# Soraduino_logsc.net
KiCad netlist of a schematic drawn in EAGLE
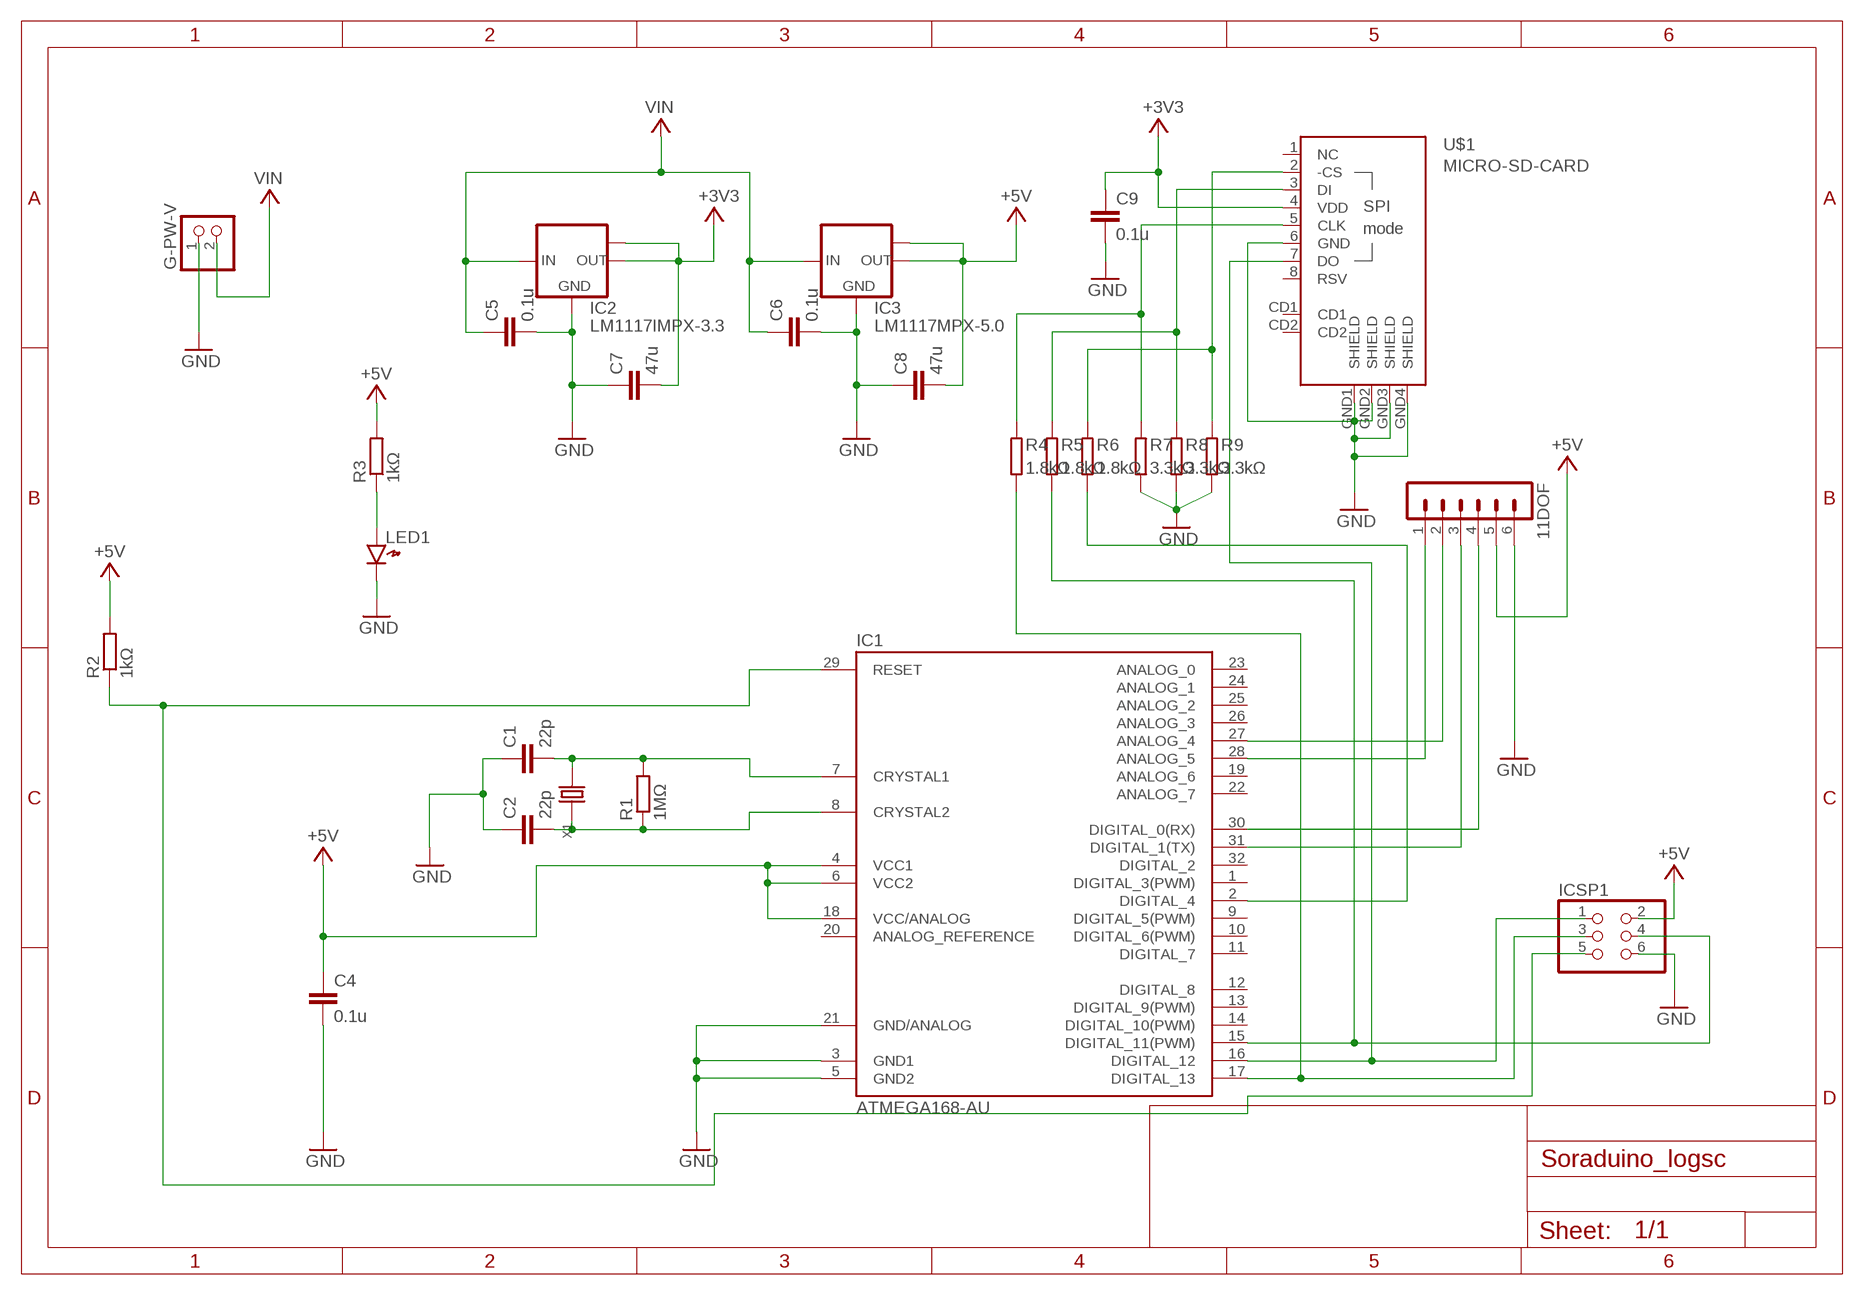
[diagram p0: schematic, sheet 1]

(export (version "E")
  (design (tool "Eeschema 10.0.6"))
  (components
    (comp (ref "11DOF")
      (value "MA06-1")
      (footprint "eagle-import:MA06-1")
      (libsource (lib "eagle-import") (part "MA06-1"))
    )
    (comp (ref "C1")
      (value "22p")
      (footprint "eagle-import:C1608")
      (libsource (lib "eagle-import") (part "C-EUC1608"))
    )
    (comp (ref "C2")
      (value "22p")
      (footprint "eagle-import:C1608")
      (libsource (lib "eagle-import") (part "C-EUC1608"))
    )
    (comp (ref "C4")
      (value "0.1u")
      (footprint "eagle-import:C2012")
      (libsource (lib "eagle-import") (part "C-EUC2012"))
    )
    (comp (ref "C5")
      (value "0.1u")
      (footprint "eagle-import:C2012")
      (libsource (lib "eagle-import") (part "C-EUC2012"))
    )
    (comp (ref "C6")
      (value "0.1u")
      (footprint "eagle-import:C2012")
      (libsource (lib "eagle-import") (part "C-EUC2012"))
    )
    (comp (ref "C7")
      (value "47u")
      (footprint "eagle-import:C3225")
      (libsource (lib "eagle-import") (part "C-EUC3225"))
    )
    (comp (ref "C8")
      (value "47u")
      (footprint "eagle-import:C3225")
      (libsource (lib "eagle-import") (part "C-EUC3225"))
    )
    (comp (ref "C9")
      (value "0.1u")
      (footprint "eagle-import:C2012")
      (libsource (lib "eagle-import") (part "C-EUC2012"))
    )
    (comp (ref "G-PW-V")
      (value "PINHD-1X2")
      (footprint "eagle-import:1X02")
      (libsource (lib "eagle-import") (part "PINHD-1X2"))
    )
    (comp (ref "IC1")
      (value "ATMEGA168-AU")
      (footprint "eagle-import:TQFP32-08")
      (libsource (lib "eagle-import") (part "ATMEGA168-AU"))
    )
    (comp (ref "IC2")
      (value "LM1117IMPX-3.3")
      (footprint "eagle-import:SOT223")
      (libsource (lib "eagle-import") (part "LM1117IMPX-3.3"))
    )
    (comp (ref "IC3")
      (value "LM1117MPX-5.0")
      (footprint "eagle-import:SOT223")
      (libsource (lib "eagle-import") (part "LM1117MPX-5.0"))
    )
    (comp (ref "ICSP1")
      (value "PINHD-2X3")
      (footprint "eagle-import:2X03")
      (libsource (lib "eagle-import") (part "PINHD-2X3"))
    )
    (comp (ref "LED1")
      (value "LED1608")
      (footprint "eagle-import:LED1608")
      (libsource (lib "eagle-import") (part "LED1608"))
    )
    (comp (ref "R1")
      (value "1MΩ")
      (footprint "eagle-import:R0603")
      (libsource (lib "eagle-import") (part "R-EU_R0603"))
    )
    (comp (ref "R2")
      (value "1kΩ")
      (footprint "eagle-import:R0603")
      (libsource (lib "eagle-import") (part "R-EU_R0603"))
    )
    (comp (ref "R3")
      (value "1kΩ")
      (footprint "eagle-import:R0603")
      (libsource (lib "eagle-import") (part "R-EU_R0603"))
    )
    (comp (ref "R4")
      (value "1.8kΩ")
      (footprint "eagle-import:SMD1608")
      (libsource (lib "eagle-import") (part "RESISTOR1608"))
    )
    (comp (ref "R5")
      (value "1.8kΩ")
      (footprint "eagle-import:SMD1608")
      (libsource (lib "eagle-import") (part "RESISTOR1608"))
    )
    (comp (ref "R6")
      (value "1.8kΩ")
      (footprint "eagle-import:SMD1608")
      (libsource (lib "eagle-import") (part "RESISTOR1608"))
    )
    (comp (ref "R7")
      (value "3.3kΩ")
      (footprint "eagle-import:SMD1608")
      (libsource (lib "eagle-import") (part "RESISTOR1608"))
    )
    (comp (ref "R8")
      (value "3.3kΩ")
      (footprint "eagle-import:SMD1608")
      (libsource (lib "eagle-import") (part "RESISTOR1608"))
    )
    (comp (ref "R9")
      (value "3.3kΩ")
      (footprint "eagle-import:SMD1608")
      (libsource (lib "eagle-import") (part "RESISTOR1608"))
    )
    (comp (ref "U$1")
      (value "MICRO-SD-CARD")
      (footprint "eagle-import:DM3AT-SF-PEJ")
      (libsource (lib "eagle-import") (part "MICRO-SD-CARD"))
    )
    (comp (ref "X1")
      (value "CRYSTAL'3225'")
      (footprint "eagle-import:4P-SMD-3.2X2.5")
      (libsource (lib "eagle-import") (part "CRYSTAL'3225'"))
    )
  )
  (nets
    (net (code "1") (name "+3V3") (class "Default")
      (node (ref "C7") (pin "2") (pinfunction "2_2") (pintype "passive"))
      (node (ref "C9") (pin "1") (pinfunction "1_1") (pintype "passive"))
      (node (ref "IC2") (pin "2") (pinfunction "OUT_2") (pintype "passive"))
      (node (ref "IC2") (pin "TAB") (pinfunction "OUT1_TAB") (pintype "passive"))
      (node (ref "U$1") (pin "4") (pinfunction "VDD_4") (pintype "bidirectional"))
    )
    (net (code "2") (name "+5V") (class "Default")
      (node (ref "11DOF") (pin "5") (pinfunction "5_5") (pintype "passive"))
      (node (ref "C4") (pin "1") (pinfunction "1_1") (pintype "passive"))
      (node (ref "C8") (pin "2") (pinfunction "2_2") (pintype "passive"))
      (node (ref "IC1") (pin "18") (pinfunction "VCC/ANALOG_18") (pintype "passive"))
      (node (ref "IC1") (pin "4") (pinfunction "VCC1_4") (pintype "power_in"))
      (node (ref "IC1") (pin "6") (pinfunction "VCC2_6") (pintype "power_in"))
      (node (ref "IC3") (pin "2") (pinfunction "OUT_2") (pintype "passive"))
      (node (ref "IC3") (pin "TAB") (pinfunction "OUT1_TAB") (pintype "passive"))
      (node (ref "ICSP1") (pin "2") (pinfunction "2_2") (pintype "passive"))
      (node (ref "R2") (pin "2") (pinfunction "2_2") (pintype "passive"))
      (node (ref "R3") (pin "2") (pinfunction "2_2") (pintype "passive"))
    )
    (net (code "3") (name "GND") (class "Default")
      (node (ref "11DOF") (pin "6") (pinfunction "6_6") (pintype "passive"))
      (node (ref "C1") (pin "1") (pinfunction "1_1") (pintype "passive"))
      (node (ref "C2") (pin "1") (pinfunction "1_1") (pintype "passive"))
      (node (ref "C4") (pin "2") (pinfunction "2_2") (pintype "passive"))
      (node (ref "C5") (pin "2") (pinfunction "2_2") (pintype "passive"))
      (node (ref "C6") (pin "2") (pinfunction "2_2") (pintype "passive"))
      (node (ref "C7") (pin "1") (pinfunction "1_1") (pintype "passive"))
      (node (ref "C8") (pin "1") (pinfunction "1_1") (pintype "passive"))
      (node (ref "C9") (pin "2") (pinfunction "2_2") (pintype "passive"))
      (node (ref "G-PW-V") (pin "1") (pinfunction "1_1") (pintype "passive"))
      (node (ref "IC1") (pin "21") (pinfunction "GND/ANALOG_21") (pintype "power_in"))
      (node (ref "IC1") (pin "3") (pinfunction "GND1_3") (pintype "power_in"))
      (node (ref "IC1") (pin "5") (pinfunction "GND2_5") (pintype "power_in"))
      (node (ref "IC2") (pin "1") (pinfunction "GND_1") (pintype "input"))
      (node (ref "IC3") (pin "1") (pinfunction "GND_1") (pintype "input"))
      (node (ref "ICSP1") (pin "6") (pinfunction "6_6") (pintype "passive"))
      (node (ref "LED1") (pin "K") (pinfunction "K_K") (pintype "passive"))
      (node (ref "R7") (pin "2") (pinfunction "2_2") (pintype "passive"))
      (node (ref "R8") (pin "2") (pinfunction "2_2") (pintype "passive"))
      (node (ref "R9") (pin "2") (pinfunction "2_2") (pintype "passive"))
      (node (ref "U$1") (pin "6") (pinfunction "GND_6") (pintype "bidirectional"))
      (node (ref "U$1") (pin "GND1") (pinfunction "SHIELD_GND1") (pintype "bidirectional"))
      (node (ref "U$1") (pin "GND2") (pinfunction "SHIELD_GND2") (pintype "bidirectional"))
      (node (ref "U$1") (pin "GND3") (pinfunction "SHIELD_GND3") (pintype "bidirectional"))
      (node (ref "U$1") (pin "GND4") (pinfunction "SHIELD_GND4") (pintype "bidirectional"))
    )
    (net (code "4") (name "Net-(IC1-ANALOG_4)") (class "Default")
      (node (ref "11DOF") (pin "2") (pinfunction "2_2") (pintype "passive"))
      (node (ref "IC1") (pin "27") (pinfunction "ANALOG_4_27") (pintype "bidirectional"))
    )
    (net (code "5") (name "Net-(IC1-ANALOG_5)") (class "Default")
      (node (ref "11DOF") (pin "1") (pinfunction "1_1") (pintype "passive"))
      (node (ref "IC1") (pin "28") (pinfunction "ANALOG_5_28") (pintype "bidirectional"))
    )
    (net (code "6") (name "Net-(IC1-CRYSTAL1)") (class "Default")
      (node (ref "C1") (pin "2") (pinfunction "2_2") (pintype "passive"))
      (node (ref "IC1") (pin "7") (pinfunction "CRYSTAL1_7") (pintype "bidirectional"))
      (node (ref "R1") (pin "2") (pinfunction "2_2") (pintype "passive"))
      (node (ref "X1") (pin "4") (pinfunction "2_4") (pintype "passive"))
    )
    (net (code "7") (name "Net-(IC1-CRYSTAL2)") (class "Default")
      (node (ref "C2") (pin "2") (pinfunction "2_2") (pintype "passive"))
      (node (ref "IC1") (pin "8") (pinfunction "CRYSTAL2_8") (pintype "bidirectional"))
      (node (ref "R1") (pin "1") (pinfunction "1_1") (pintype "passive"))
      (node (ref "X1") (pin "2") (pinfunction "1_2") (pintype "passive"))
    )
    (net (code "8") (name "Net-(IC1-DIGITAL_0(RX))") (class "Default")
      (node (ref "11DOF") (pin "4") (pinfunction "4_4") (pintype "passive"))
      (node (ref "IC1") (pin "30") (pinfunction "DIGITAL_0(RX)_30") (pintype "bidirectional"))
    )
    (net (code "9") (name "Net-(IC1-DIGITAL_1(TX))") (class "Default")
      (node (ref "11DOF") (pin "3") (pinfunction "3_3") (pintype "passive"))
      (node (ref "IC1") (pin "31") (pinfunction "DIGITAL_1(TX)_31") (pintype "bidirectional"))
    )
    (net (code "10") (name "Net-(IC1-DIGITAL_4)") (class "Default")
      (node (ref "IC1") (pin "2") (pinfunction "DIGITAL_4_2") (pintype "bidirectional"))
      (node (ref "R6") (pin "2") (pinfunction "2_2") (pintype "passive"))
    )
    (net (code "11") (name "Net-(IC1-DIGITAL_11(PWM))") (class "Default")
      (node (ref "IC1") (pin "15") (pinfunction "DIGITAL_11(PWM)_15") (pintype "bidirectional"))
      (node (ref "ICSP1") (pin "4") (pinfunction "4_4") (pintype "passive"))
      (node (ref "R5") (pin "2") (pinfunction "2_2") (pintype "passive"))
    )
    (net (code "12") (name "Net-(IC1-DIGITAL_12)") (class "Default")
      (node (ref "IC1") (pin "16") (pinfunction "DIGITAL_12_16") (pintype "bidirectional"))
      (node (ref "ICSP1") (pin "1") (pinfunction "1_1") (pintype "passive"))
      (node (ref "U$1") (pin "7") (pinfunction "DO_7") (pintype "bidirectional"))
    )
    (net (code "13") (name "Net-(IC1-DIGITAL_13)") (class "Default")
      (node (ref "IC1") (pin "17") (pinfunction "DIGITAL_13_17") (pintype "bidirectional"))
      (node (ref "ICSP1") (pin "3") (pinfunction "3_3") (pintype "passive"))
      (node (ref "R4") (pin "2") (pinfunction "2_2") (pintype "passive"))
    )
    (net (code "14") (name "Net-(IC1-RESET)") (class "Default")
      (node (ref "IC1") (pin "29") (pinfunction "RESET_29") (pintype "bidirectional"))
      (node (ref "ICSP1") (pin "5") (pinfunction "5_5") (pintype "passive"))
      (node (ref "R2") (pin "1") (pinfunction "1_1") (pintype "passive"))
    )
    (net (code "15") (name "Net-(LED1-PadA)") (class "Default")
      (node (ref "LED1") (pin "A") (pinfunction "A_A") (pintype "passive"))
      (node (ref "R3") (pin "1") (pinfunction "1_1") (pintype "passive"))
    )
    (net (code "16") (name "Net-(U$1--CS)") (class "Default")
      (node (ref "R6") (pin "1") (pinfunction "1_1") (pintype "passive"))
      (node (ref "R9") (pin "1") (pinfunction "1_1") (pintype "passive"))
      (node (ref "U$1") (pin "2") (pinfunction "-CS_2") (pintype "bidirectional"))
    )
    (net (code "17") (name "Net-(U$1-CLK)") (class "Default")
      (node (ref "R4") (pin "1") (pinfunction "1_1") (pintype "passive"))
      (node (ref "R7") (pin "1") (pinfunction "1_1") (pintype "passive"))
      (node (ref "U$1") (pin "5") (pinfunction "CLK_5") (pintype "bidirectional"))
    )
    (net (code "18") (name "Net-(U$1-DI)") (class "Default")
      (node (ref "R5") (pin "1") (pinfunction "1_1") (pintype "passive"))
      (node (ref "R8") (pin "1") (pinfunction "1_1") (pintype "passive"))
      (node (ref "U$1") (pin "3") (pinfunction "DI_3") (pintype "bidirectional"))
    )
    (net (code "19") (name "VIN") (class "Default")
      (node (ref "C5") (pin "1") (pinfunction "1_1") (pintype "passive"))
      (node (ref "C6") (pin "1") (pinfunction "1_1") (pintype "passive"))
      (node (ref "G-PW-V") (pin "2") (pinfunction "2_2") (pintype "passive"))
      (node (ref "IC2") (pin "3") (pinfunction "IN_3") (pintype "input"))
      (node (ref "IC3") (pin "3") (pinfunction "IN_3") (pintype "input"))
    )
    (net (code "20") (name "unconnected-(IC1-ANALOG_0-Pad23)") (class "Default")
      (node (ref "IC1") (pin "23") (pinfunction "ANALOG_0_23") (pintype "bidirectional"))
    )
    (net (code "21") (name "unconnected-(IC1-ANALOG_1-Pad24)") (class "Default")
      (node (ref "IC1") (pin "24") (pinfunction "ANALOG_1_24") (pintype "bidirectional"))
    )
    (net (code "22") (name "unconnected-(IC1-ANALOG_2-Pad25)") (class "Default")
      (node (ref "IC1") (pin "25") (pinfunction "ANALOG_2_25") (pintype "bidirectional"))
    )
    (net (code "23") (name "unconnected-(IC1-ANALOG_3-Pad26)") (class "Default")
      (node (ref "IC1") (pin "26") (pinfunction "ANALOG_3_26") (pintype "bidirectional"))
    )
    (net (code "24") (name "unconnected-(IC1-ANALOG_6-Pad19)") (class "Default")
      (node (ref "IC1") (pin "19") (pinfunction "ANALOG_6_19") (pintype "passive"))
    )
    (net (code "25") (name "unconnected-(IC1-ANALOG_7-Pad22)") (class "Default")
      (node (ref "IC1") (pin "22") (pinfunction "ANALOG_7_22") (pintype "passive"))
    )
    (net (code "26") (name "unconnected-(IC1-ANALOG_REFERENCE-Pad20)") (class "Default")
      (node (ref "IC1") (pin "20") (pinfunction "ANALOG_REFERENCE_20") (pintype "passive"))
    )
    (net (code "27") (name "unconnected-(IC1-DIGITAL_2-Pad32)") (class "Default")
      (node (ref "IC1") (pin "32") (pinfunction "DIGITAL_2_32") (pintype "bidirectional"))
    )
    (net (code "28") (name "unconnected-(IC1-DIGITAL_3(PWM)-Pad1)") (class "Default")
      (node (ref "IC1") (pin "1") (pinfunction "DIGITAL_3(PWM)_1") (pintype "bidirectional"))
    )
    (net (code "29") (name "unconnected-(IC1-DIGITAL_5(PWM)-Pad9)") (class "Default")
      (node (ref "IC1") (pin "9") (pinfunction "DIGITAL_5(PWM)_9") (pintype "bidirectional"))
    )
    (net (code "30") (name "unconnected-(IC1-DIGITAL_6(PWM)-Pad10)") (class "Default")
      (node (ref "IC1") (pin "10") (pinfunction "DIGITAL_6(PWM)_10") (pintype "bidirectional"))
    )
    (net (code "31") (name "unconnected-(IC1-DIGITAL_7-Pad11)") (class "Default")
      (node (ref "IC1") (pin "11") (pinfunction "DIGITAL_7_11") (pintype "bidirectional"))
    )
    (net (code "32") (name "unconnected-(IC1-DIGITAL_8-Pad12)") (class "Default")
      (node (ref "IC1") (pin "12") (pinfunction "DIGITAL_8_12") (pintype "bidirectional"))
    )
    (net (code "33") (name "unconnected-(IC1-DIGITAL_9(PWM)-Pad13)") (class "Default")
      (node (ref "IC1") (pin "13") (pinfunction "DIGITAL_9(PWM)_13") (pintype "bidirectional"))
    )
    (net (code "34") (name "unconnected-(IC1-DIGITAL_10(PWM)-Pad14)") (class "Default")
      (node (ref "IC1") (pin "14") (pinfunction "DIGITAL_10(PWM)_14") (pintype "bidirectional"))
    )
    (net (code "35") (name "unconnected-(U$1-NC-Pad1)") (class "Default")
      (node (ref "U$1") (pin "1") (pinfunction "NC_1") (pintype "bidirectional"))
    )
    (net (code "36") (name "unconnected-(U$1-PadCD1)") (class "Default")
      (node (ref "U$1") (pin "CD1") (pinfunction "CD1_CD1") (pintype "bidirectional"))
    )
    (net (code "37") (name "unconnected-(U$1-PadCD2)") (class "Default")
      (node (ref "U$1") (pin "CD2") (pinfunction "CD2_CD2") (pintype "bidirectional"))
    )
    (net (code "38") (name "unconnected-(U$1-RSV-Pad8)") (class "Default")
      (node (ref "U$1") (pin "8") (pinfunction "RSV_8") (pintype "bidirectional"))
    )
  )
)
